# RML.net
KiCad netlist of a schematic drawn in Altium Designer
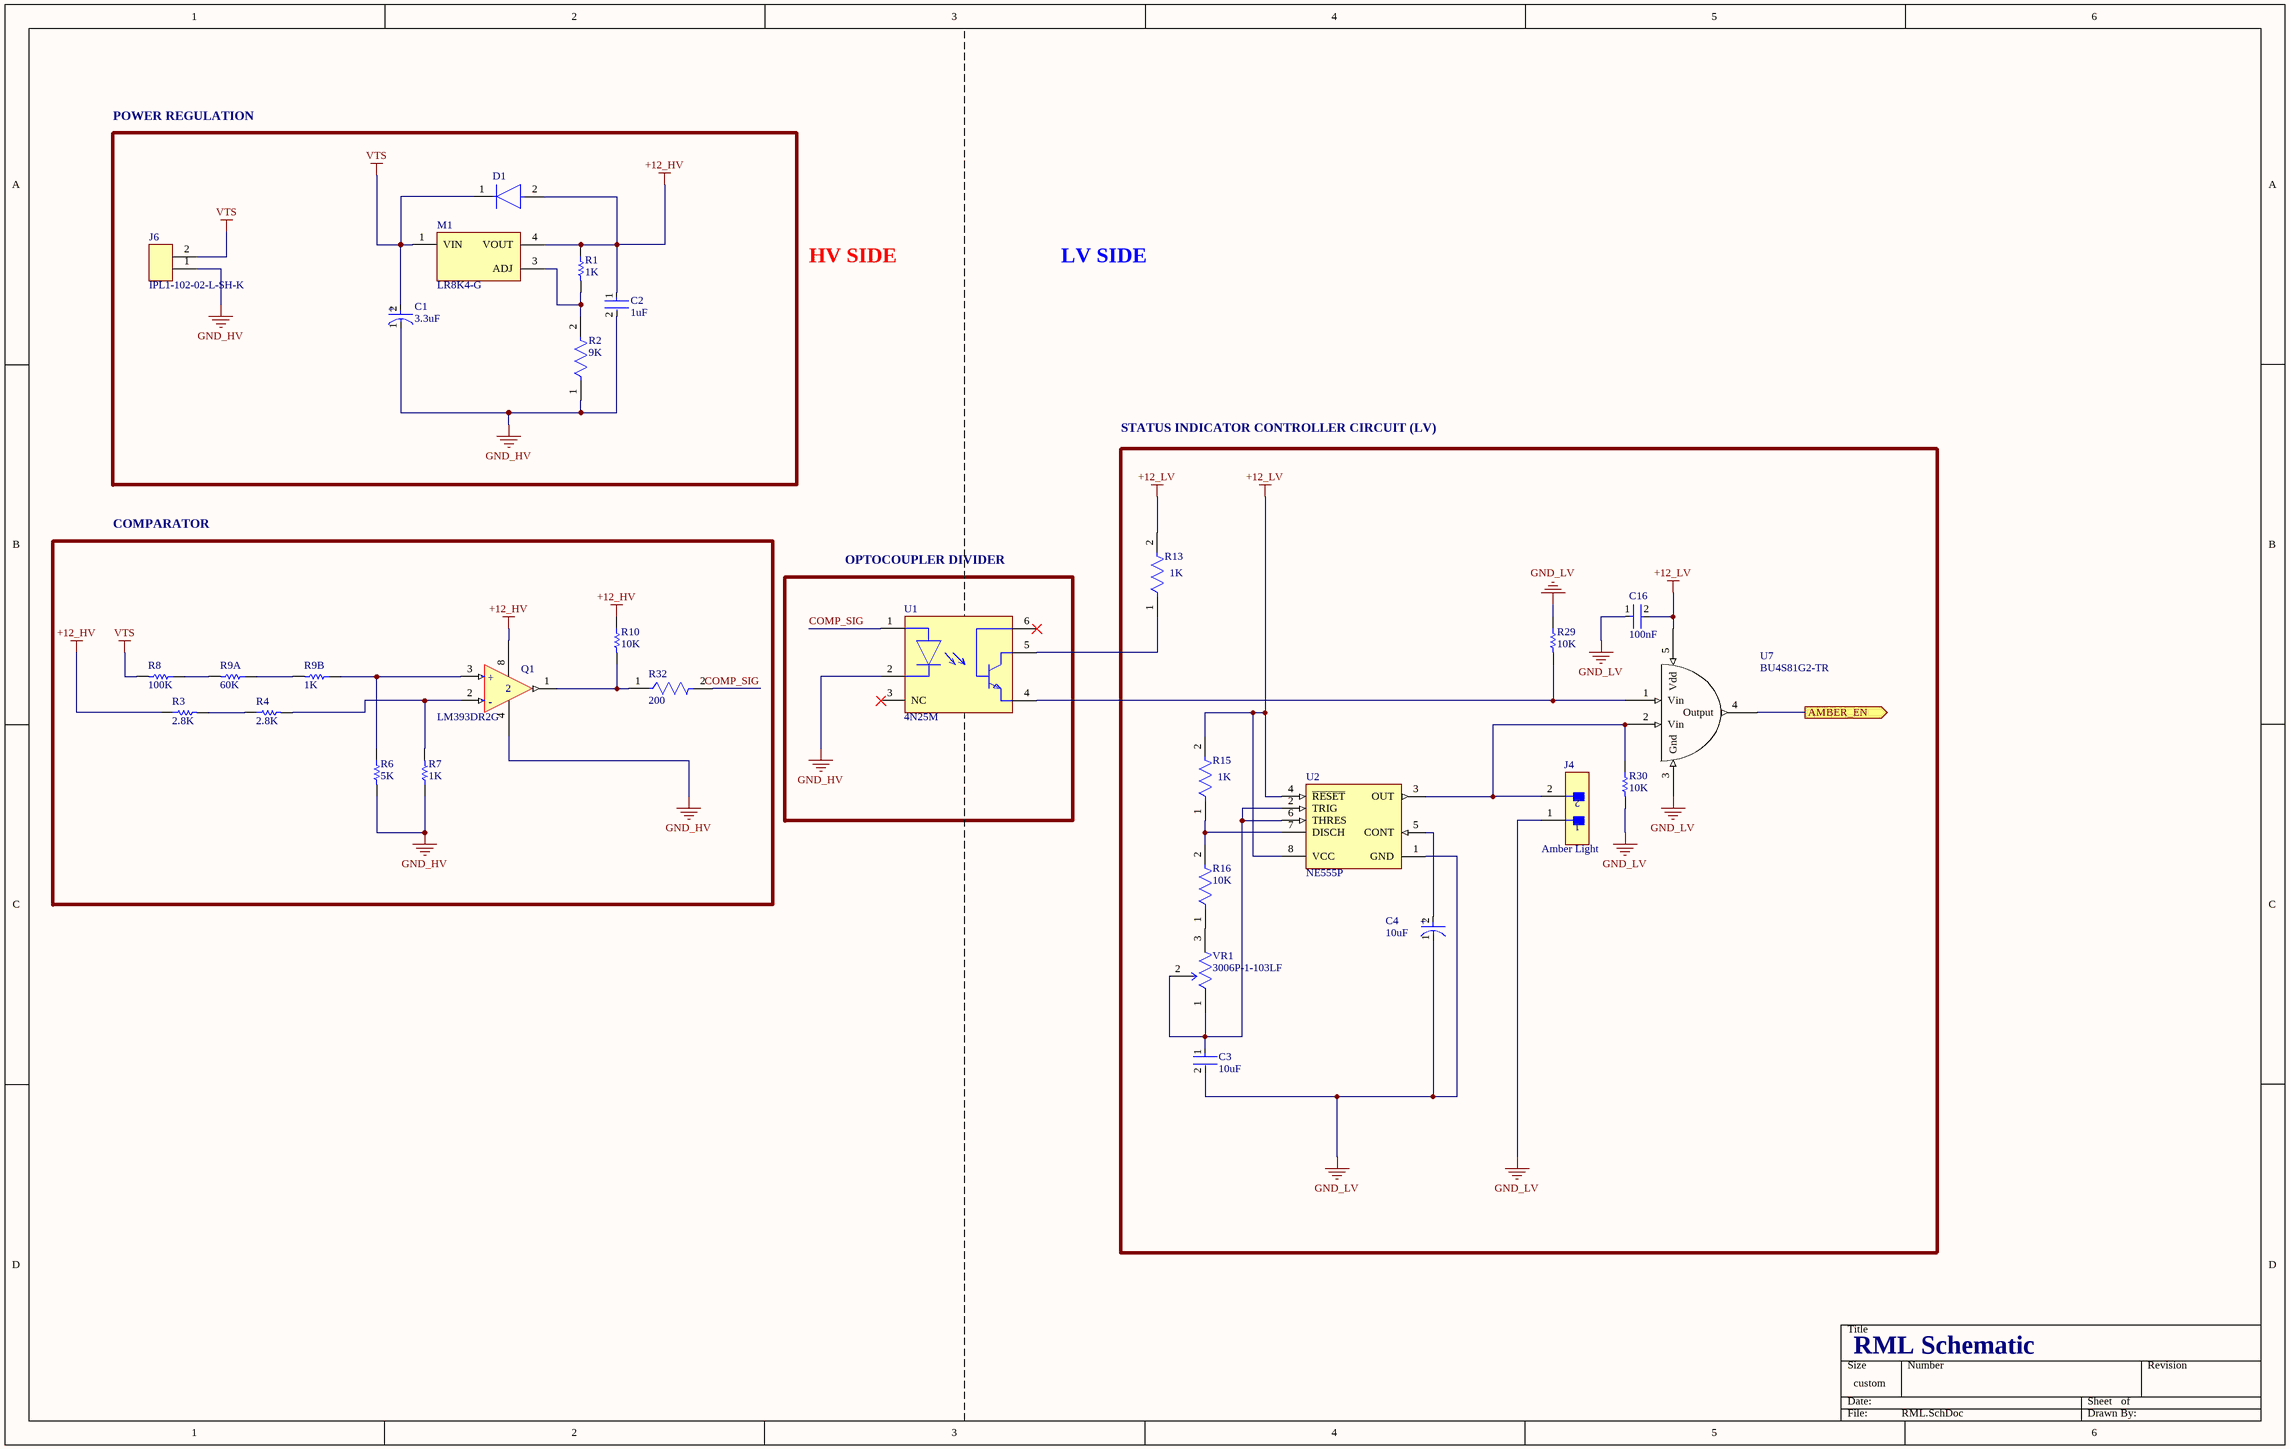
[diagram p0: RML.SchDoc]

(export (version "E")
  (design (tool "Eeschema 10.0.6"))
  (components
    (comp (ref "C1")
      (value "3.3uF")
      (footprint "FP-RAD-TH-D_10_0_5-L_12_5-MFG")
      (description "Aluminum Electrolytic Capacitors (Radial Lead Type) 3.3uF ±20% 400V")
      (fields (field (name "TOLERANCE") "20%") (field (name "VOLTAGE") "400V"))
      (libsource (lib "Altium Content Vault") (part "203bc49f2ac43e59fd269a8c329ed05"))
    )
    (comp (ref "C2")
      (value "1uF")
      (footprint "FP-RCE2K1-MFG")
      (libsource (lib "Ontario Tech Racing New") (part "02cd4be3c70576c341d710602a673aa"))
    )
    (comp (ref "C3")
      (value "10uF")
      (footprint "FP-RCE3DB-MFG")
      (libsource (lib "Ontario Tech Racing New") (part "b4654b650e69147ec39a6b967a45e02"))
    )
    (comp (ref "C4")
      (value "10uF")
      (footprint "FP-RAD-TH-D_5_0_5-L_11_1-MFG")
      (libsource (lib "Ontario Tech Racing New") (part "a00bbbee19879c290e62620ae7e47b1"))
    )
    (comp (ref "C16")
      (value "100nF")
      (footprint "FP-C1206C-EB-MFG")
      (description "CAP CER 0.1UF 100V X7R 1206")
      (fields
        (field (name "TOLERANCE") "0.1")
        (field (name "OCTOPART") "https://octopart.com/c1206c104k1ractu-kemet-89521")
      )
      (libsource (lib "Altium Content Vault") (part "b4654b650e69147ec39a6b967a45e02"))
    )
    (comp (ref "D1")
      (value "1N4007-TP")
      (footprint "FP-1N4007-TP-MFG")
      (description "DIODE GEN PURP 1KV 1A DO41")
      (libsource (lib "Altium Content Vault") (part "d7152d700b627762746794eb795d46e"))
    )
    (comp (ref "J4")
      (value "Amber Light")
      (footprint "FP-M20-9990246-MFG")
      (description "CONN HEADER VERT 2POS 2.54MM")
      (fields
        (field (name "OCTOPART") "https://octopart.com/m20-9990246-harwin-2590635")
        (field (name "MANUFACTURER") "Harwin")
      )
      (libsource (lib "Altium Content Vault") (part "3bc925449376181038e59eaffc5286c"))
    )
    (comp (ref "J6")
      (value "IPL1-102-02-L-SH-K")
      (footprint "J__SAMTEC_IPL1-102-02-XXX-SH-K")
      (description "Connector Header Surface Mount, Right Angle 2 position 0.100\" (2.54mm)")
      (fields (field (name "MANUFACTURER") "Samtec"))
      (libsource (lib "Ontario Tech Racing New") (part "J__GENERIC__2_POS__1_ROW"))
    )
    (comp (ref "M1")
      (value "LR8K4-G")
      (footprint "FP-C04-189-MFG")
      (description "Linear Voltage Regulator IC Positive Adjustable 1 Output 10mA TO-252, (D-Pak)")
      (fields (field (name "OCTOPART") "https://octopart.com/lr8k4-g-microchip-47153542"))
      (libsource (lib "Altium Content Vault") (part "1528d5d37afbf9721ed6de1dfab59b2"))
    )
    (comp (ref "Q1")
      (value "LM393DR2G")
      (footprint "SOIC8_ONSEMI_LM393DR2G_2N")
      (description "Comparator General Purpose Open-Collector, Rail-to-Rail 8-SOIC")
      (fields (field (name "MANUFACTURER") "Onsemi"))
      (libsource (lib "Ontario Tech Racing New") (part "SOIC8_ONSEMI_LM393DR2G_2"))
    )
    (comp (ref "R1")
      (value "1K")
      (footprint "R_1206_YAGEO_AC")
      (description "RES SMD 1K OHM 1% 1/4W 1206")
      (fields (field (name "MANUFACTURER") "YAGEO") (field (name "TOLERANCE") "1%"))
      (libsource (lib "Ontario Tech Racing New") (part "resistor-1"))
    )
    (comp (ref "R2")
      (value "9K")
      (footprint "FP-MCA1206-IPC_B")
      (description "Fixed Resistor, Thin Film, 0.25W, 9000ohm, 200V, 0.1% +/-Tol, 25ppm/Cel, Surface Mount, 1206")
      (fields (field (name "TOLERANCE") "0.1%"))
      (libsource (lib "Ontario Tech Racing New") (part "1029c3af85768c4190bb7ad29bc67b5"))
    )
    (comp (ref "R3")
      (value "2.8K")
      (footprint "RESC3116X65X40ML10T20")
      (fields (field (name "TOLERANCE") "1%"))
      (libsource (lib "Ontario Tech Racing New") (part "RES"))
    )
    (comp (ref "R4")
      (value "2.8K")
      (footprint "RESC3116X65X40ML10T20")
      (fields (field (name "TOLERANCE") "1%"))
      (libsource (lib "Ontario Tech Racing New") (part "RES"))
    )
    (comp (ref "R6")
      (value "5K")
      (footprint "R_2512_YAGEO_AC")
      (description "RES SMD 4.99K OHM 1% 1W 2512")
      (fields (field (name "TOLERANCE") "1%") (field (name "MANUFACTURER") "YAGEO"))
      (libsource (lib "Ontario Tech Racing New") (part "resistor-1"))
    )
    (comp (ref "R7")
      (value "1K")
      (footprint "R_1206_YAGEO_AC")
      (description "RES SMD 1K OHM 1% 1/4W 1206")
      (fields (field (name "MANUFACTURER") "YAGEO") (field (name "TOLERANCE") "1%"))
      (libsource (lib "Ontario Tech Racing New") (part "resistor-1"))
    )
    (comp (ref "R8")
      (value "100K")
      (footprint "R_2512_YAGEO_AC")
      (description "RES SMD 100K OHM 1% 1W 2512")
      (fields (field (name "MANUFACTURER") "YAGEO") (field (name "TOLERANCE") "1%"))
      (libsource (lib "Ontario Tech Racing New") (part "resistor-1"))
    )
    (comp (ref "R9A")
      (value "60K")
      (footprint "RESC__2512__VISHAY_DALE__20035N")
      (description "RES SMD 60.4K OHM 1% 1W 2512")
      (fields (field (name "TOLERANCE") "5%") (field (name "MANUFACTURER") "Vishay Dale"))
      (libsource (lib "Ontario Tech Racing New") (part "RESC__2512__VISHAY_DALE__20035N"))
    )
    (comp (ref "R9B")
      (value "1K")
      (footprint "R_2512_YAGEO_AC")
      (description "RES SMD 1K OHM 1% 1W 2512")
      (fields (field (name "TOLERANCE") "1%") (field (name "MANUFACTURER") "YAGEO"))
      (libsource (lib "Ontario Tech Racing New") (part "resistor-1"))
    )
    (comp (ref "R10")
      (value "10K")
      (footprint "R_1206_YAGEO_AC")
      (description "RES SMD 10K OHM 1% 1/4W 1206")
      (fields (field (name "MANUFACTURER") "YAGEO") (field (name "TOLERANCE") "1%"))
      (libsource (lib "Ontario Tech Racing New") (part "resistor-1"))
    )
    (comp (ref "R13")
      (value "1K")
      (footprint "FP-RLR07-MFG")
      (fields (field (name "TOLERANCE") "1%"))
      (libsource (lib "Altium Content Vault") (part "1029c3af85768c4190bb7ad29bc67b5"))
    )
    (comp (ref "R15")
      (value "1K")
      (footprint "FP-RLR07-MFG")
      (fields (field (name "TOLERANCE") "1%"))
      (libsource (lib "Altium Content Vault") (part "1029c3af85768c4190bb7ad29bc67b5"))
    )
    (comp (ref "R16")
      (value "10K")
      (footprint "FP-RLR07-MFG")
      (description "Fixed Resistor, Metal Film, 0.25W, 100000ohm, 250V, 1% +/-Tol, 100ppm/Cel, Through Hole Mount")
      (fields (field (name "TOLERANCE") "1%"))
      (libsource (lib "Ontario Tech Racing New") (part "1029c3af85768c4190bb7ad29bc67b5"))
    )
    (comp (ref "R29")
      (value "10K")
      (footprint "R_1206_YAGEO_AC")
      (description "RES SMD 10K OHM 1% 1/4W 1206")
      (fields (field (name "MANUFACTURER") "YAGEO") (field (name "TOLERANCE") "1%"))
      (libsource (lib "Ontario Tech Racing New") (part "resistor-1"))
    )
    (comp (ref "R30")
      (value "10K")
      (footprint "R_1206_YAGEO_AC")
      (description "RES SMD 10K OHM 1% 1/4W 1206")
      (fields (field (name "MANUFACTURER") "YAGEO") (field (name "TOLERANCE") "1%"))
      (libsource (lib "Ontario Tech Racing New") (part "resistor-1"))
    )
    (comp (ref "R32")
      (value "200")
      (footprint "FP-RMCF1206-IPC_A")
      (description "220Ω ±5% 0.25W 1206 Thick Film Chip Resistor AEC-Q200 compliant")
      (fields (field (name "TOLERANCE") "5%"))
      (libsource (lib "Altium Content Vault") (part "1029c3af85768c4190bb7ad29bc67b5"))
    )
    (comp (ref "U1")
      (value "4N25M")
      (footprint "FP-646BX-MFG")
      (description "4N25M Optocoupler DC-IN 1-CH Transistor With Base DC-OUT 6-Pin PDIP Tube - Bulk")
      (libsource (lib "Altium Content Vault") (part "60cd882971725889b330b3d3aa4682b"))
    )
    (comp (ref "U2")
      (value "NE555P")
      (footprint "P0008A")
      (description "Precision Timer, 4.5 to 16 V, 0 to 70 degC, 8-Pin DIP, Pb-Free, Tube")
      (fields (field (name "MANUFACTURER") "TexasInstruments"))
      (libsource (lib "Altium Content Vault") (part "TI-NE555-P8"))
    )
    (comp (ref "U7")
      (value "BU4S81G2-TR")
      (footprint "SSOP5__ROHM_SEMICONDUCTOR__TSZ02201-0RDR0GZ00200-1-2")
      (description "IC GATE AND 1CH 2-INP 5SSOP")
      (libsource (lib "Ontario Tech Racing New") (part "BU4S81G2-TR"))
    )
    (comp (ref "VR1")
      (value "3006P-1-103LF")
      (footprint "FP-3006P-MFG")
      (description "TRIMMER 10KOHM 0.75W PC PIN SIDE")
      (fields (field (name "TOLERANCE") "10%"))
      (libsource (lib "Altium Content Vault") (part "ad0de4570dda44d2fdef8f57041519a"))
    )
  )
  (nets
    (net (code "1") (name "+12_HV") (class "Default")
      (node (ref "C2") (pin "1") (pinfunction "1_1") (pintype "passive"))
      (node (ref "D1") (pin "2") (pinfunction "A_2") (pintype "passive"))
      (node (ref "M1") (pin "4") (pinfunction "VOUT_4") (pintype "power_in"))
      (node (ref "Q1") (pin "8") (pinfunction "VCC_(+)_8") (pintype "passive"))
      (node (ref "R1") (pin "1") (pinfunction "1_1") (pintype "passive"))
      (node (ref "R10") (pin "1") (pinfunction "1_1") (pintype "passive"))
      (node (ref "R3") (pin "1") (pinfunction "1_1") (pintype "passive"))
    )
    (net (code "2") (name "+12_LV") (class "Default")
      (node (ref "C16") (pin "2") (pinfunction "2_2") (pintype "passive"))
      (node (ref "R13") (pin "2") (pinfunction "2_2") (pintype "passive"))
      (node (ref "R15") (pin "2") (pinfunction "2_2") (pintype "passive"))
      (node (ref "U2") (pin "4") (pinfunction "~{RESET}_4") (pintype "input"))
      (node (ref "U2") (pin "8") (pinfunction "VCC_8") (pintype "power_in"))
      (node (ref "U7") (pin "5") (pinfunction "Vdd_5") (pintype "input"))
    )
    (net (code "3") (name "/AMBER_EN") (class "Default")
      (node (ref "U7") (pin "4") (pinfunction "Output_4") (pintype "output"))
    )
    (net (code "4") (name "/COMP_SIG") (class "Default")
      (node (ref "R32") (pin "2") (pinfunction "2_2") (pintype "passive"))
      (node (ref "U1") (pin "1") (pinfunction "A_1") (pintype "passive"))
    )
    (net (code "5") (name "GND_HV") (class "Default")
      (node (ref "C1") (pin "1") (pinfunction "C_1") (pintype "passive"))
      (node (ref "C2") (pin "2") (pinfunction "2_2") (pintype "passive"))
      (node (ref "J6") (pin "1") (pintype "passive"))
      (node (ref "Q1") (pin "4") (pinfunction "VCC_(-)_4") (pintype "passive"))
      (node (ref "R2") (pin "1") (pinfunction "1_1") (pintype "passive"))
      (node (ref "R6") (pin "2") (pinfunction "2_2") (pintype "passive"))
      (node (ref "R7") (pin "1") (pinfunction "1_1") (pintype "passive"))
      (node (ref "U1") (pin "2") (pinfunction "C_2") (pintype "passive"))
    )
    (net (code "6") (name "GND_LV") (class "Default")
      (node (ref "C16") (pin "1") (pinfunction "1_1") (pintype "passive"))
      (node (ref "C3") (pin "2") (pinfunction "2_2") (pintype "passive"))
      (node (ref "C4") (pin "1") (pinfunction "C_1") (pintype "passive"))
      (node (ref "J4") (pin "1") (pinfunction "1_1") (pintype "passive"))
      (node (ref "R29") (pin "1") (pinfunction "1_1") (pintype "passive"))
      (node (ref "R30") (pin "2") (pinfunction "2_2") (pintype "passive"))
      (node (ref "U2") (pin "1") (pinfunction "GND_1") (pintype "power_in"))
      (node (ref "U7") (pin "3") (pinfunction "Gnd_3") (pintype "input"))
    )
    (net (code "7") (name "Net-(C4-A)") (class "Default")
      (node (ref "C4") (pin "2") (pinfunction "A_2") (pintype "passive"))
      (node (ref "U2") (pin "5") (pinfunction "CONT_5") (pintype "input"))
    )
    (net (code "8") (name "Net-(M1-ADJ)") (class "Default")
      (node (ref "M1") (pin "3") (pinfunction "ADJ_3") (pintype "passive"))
      (node (ref "R1") (pin "2") (pinfunction "2_2") (pintype "passive"))
      (node (ref "R2") (pin "2") (pinfunction "2_2") (pintype "passive"))
    )
    (net (code "9") (name "Net-(Q1-INPUT_B+)") (class "Default")
      (node (ref "Q1") (pin "3") (pinfunction "INPUT_B+_3") (pintype "input"))
      (node (ref "R6") (pin "1") (pinfunction "1_1") (pintype "passive"))
      (node (ref "R9B") (pin "1") (pinfunction "1_1") (pintype "passive"))
    )
    (net (code "10") (name "Net-(Q1-INPUT_B-)") (class "Default")
      (node (ref "Q1") (pin "2") (pinfunction "INPUT_B-_2") (pintype "input"))
      (node (ref "R4") (pin "2") (pinfunction "2_2") (pintype "passive"))
      (node (ref "R7") (pin "2") (pinfunction "2_2") (pintype "passive"))
    )
    (net (code "11") (name "Net-(Q1-OUTPUT_B)") (class "Default")
      (node (ref "Q1") (pin "1") (pinfunction "OUTPUT_B_1") (pintype "output"))
      (node (ref "R10") (pin "2") (pinfunction "2_2") (pintype "passive"))
      (node (ref "R32") (pin "1") (pinfunction "1_1") (pintype "passive"))
    )
    (net (code "12") (name "Net-(R3-Pad2)") (class "Default")
      (node (ref "R3") (pin "2") (pinfunction "2_2") (pintype "passive"))
      (node (ref "R4") (pin "1") (pinfunction "1_1") (pintype "passive"))
    )
    (net (code "13") (name "Net-(R8-Pad1)") (class "Default")
      (node (ref "R8") (pin "1") (pinfunction "1_1") (pintype "passive"))
      (node (ref "R9A") (pin "2") (pinfunction "2_2") (pintype "passive"))
    )
    (net (code "14") (name "Net-(R9A-Pad1)") (class "Default")
      (node (ref "R9A") (pin "1") (pinfunction "1_1") (pintype "passive"))
      (node (ref "R9B") (pin "2") (pinfunction "2_2") (pintype "passive"))
    )
    (net (code "15") (name "Net-(R13-Pad1)") (class "Default")
      (node (ref "R13") (pin "1") (pinfunction "1_1") (pintype "passive"))
      (node (ref "U1") (pin "5") (pinfunction "C_5") (pintype "passive"))
    )
    (net (code "16") (name "Net-(U1-E)") (class "Default")
      (node (ref "R29") (pin "2") (pinfunction "2_2") (pintype "passive"))
      (node (ref "U1") (pin "4") (pinfunction "E_4") (pintype "passive"))
      (node (ref "U7") (pin "1") (pinfunction "Vin_1") (pintype "input"))
    )
    (net (code "17") (name "Net-(U2-DISCH)") (class "Default")
      (node (ref "R15") (pin "1") (pinfunction "1_1") (pintype "passive"))
      (node (ref "R16") (pin "2") (pinfunction "2_2") (pintype "passive"))
      (node (ref "U2") (pin "7") (pinfunction "DISCH_7") (pintype "open_collector"))
    )
    (net (code "18") (name "Net-(U2-OUT)") (class "Default")
      (node (ref "J4") (pin "2") (pinfunction "2_2") (pintype "passive"))
      (node (ref "R30") (pin "1") (pinfunction "1_1") (pintype "passive"))
      (node (ref "U2") (pin "3") (pinfunction "OUT_3") (pintype "output"))
      (node (ref "U7") (pin "2") (pinfunction "Vin_2") (pintype "input"))
    )
    (net (code "19") (name "Net-(U2-THRES)") (class "Default")
      (node (ref "C3") (pin "1") (pinfunction "1_1") (pintype "passive"))
      (node (ref "U2") (pin "2") (pinfunction "TRIG_2") (pintype "input"))
      (node (ref "U2") (pin "6") (pinfunction "THRES_6") (pintype "input"))
      (node (ref "VR1") (pin "1") (pinfunction "CCW_1") (pintype "passive"))
      (node (ref "VR1") (pin "2") (pinfunction "WIPER_2") (pintype "passive"))
    )
    (net (code "20") (name "Net-(VR1-CW)") (class "Default")
      (node (ref "R16") (pin "1") (pinfunction "1_1") (pintype "passive"))
      (node (ref "VR1") (pin "3") (pinfunction "CW_3") (pintype "passive"))
    )
    (net (code "21") (name "VTS") (class "Default")
      (node (ref "C1") (pin "2") (pinfunction "A_2") (pintype "passive"))
      (node (ref "D1") (pin "1") (pinfunction "C_1") (pintype "passive"))
      (node (ref "J6") (pin "2") (pintype "passive"))
      (node (ref "M1") (pin "1") (pinfunction "VIN_1") (pintype "power_in"))
      (node (ref "R8") (pin "2") (pinfunction "2_2") (pintype "passive"))
    )
    (net (code "22") (name "unconnected-(U1-B-Pad6)") (class "Default")
      (node (ref "U1") (pin "6") (pinfunction "B_6") (pintype "passive+no_connect"))
    )
    (net (code "23") (name "unconnected-(U1-NC-Pad3)") (class "Default")
      (node (ref "U1") (pin "3") (pinfunction "NC_3") (pintype "passive+no_connect"))
    )
  )
)
